# EEZ_DIB_AUX_PS_r1B2.net
KiCad netlist of a schematic drawn in EAGLE
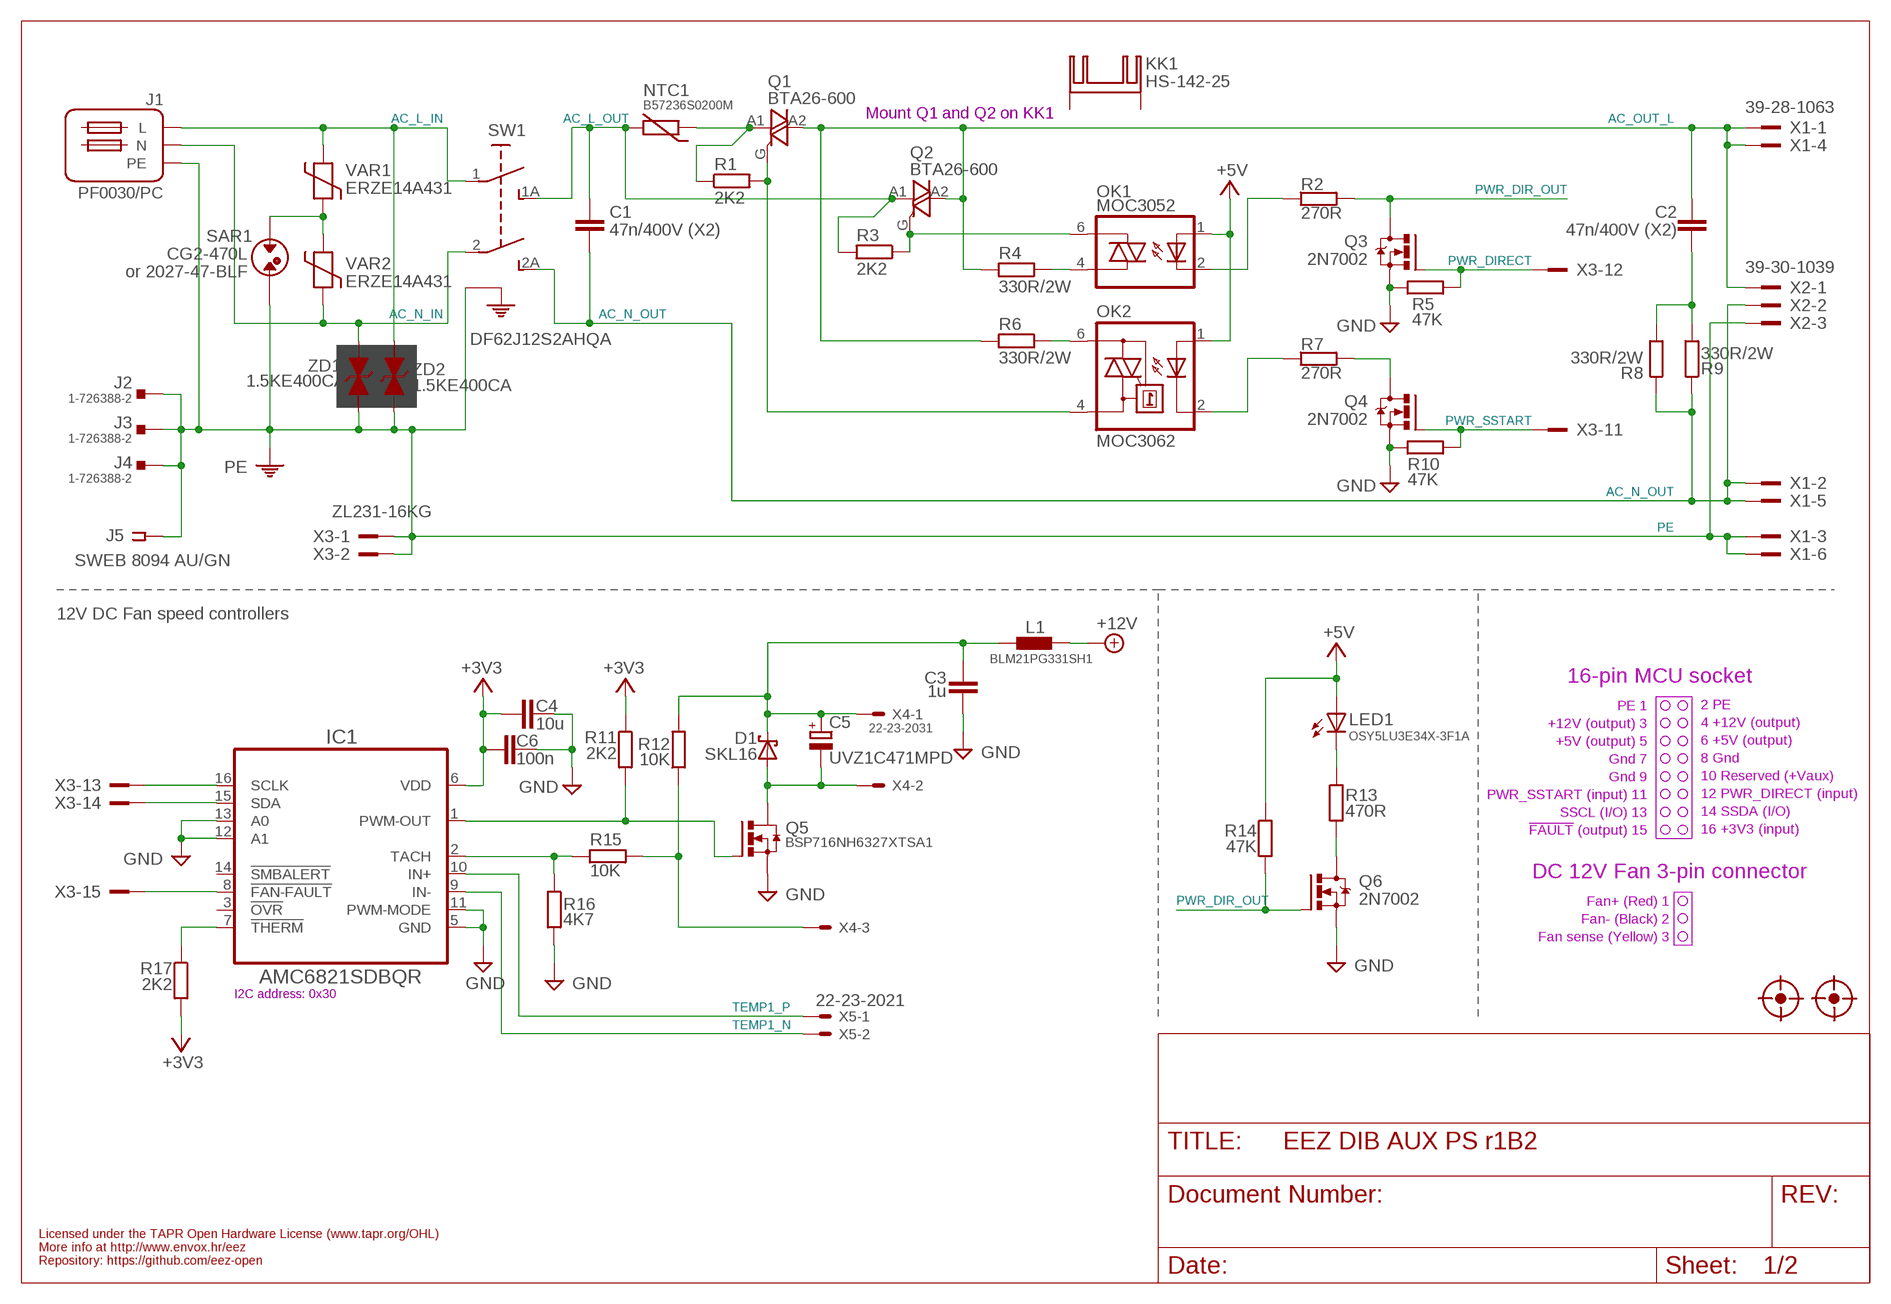
[diagram p0: schematic, sheet 1]
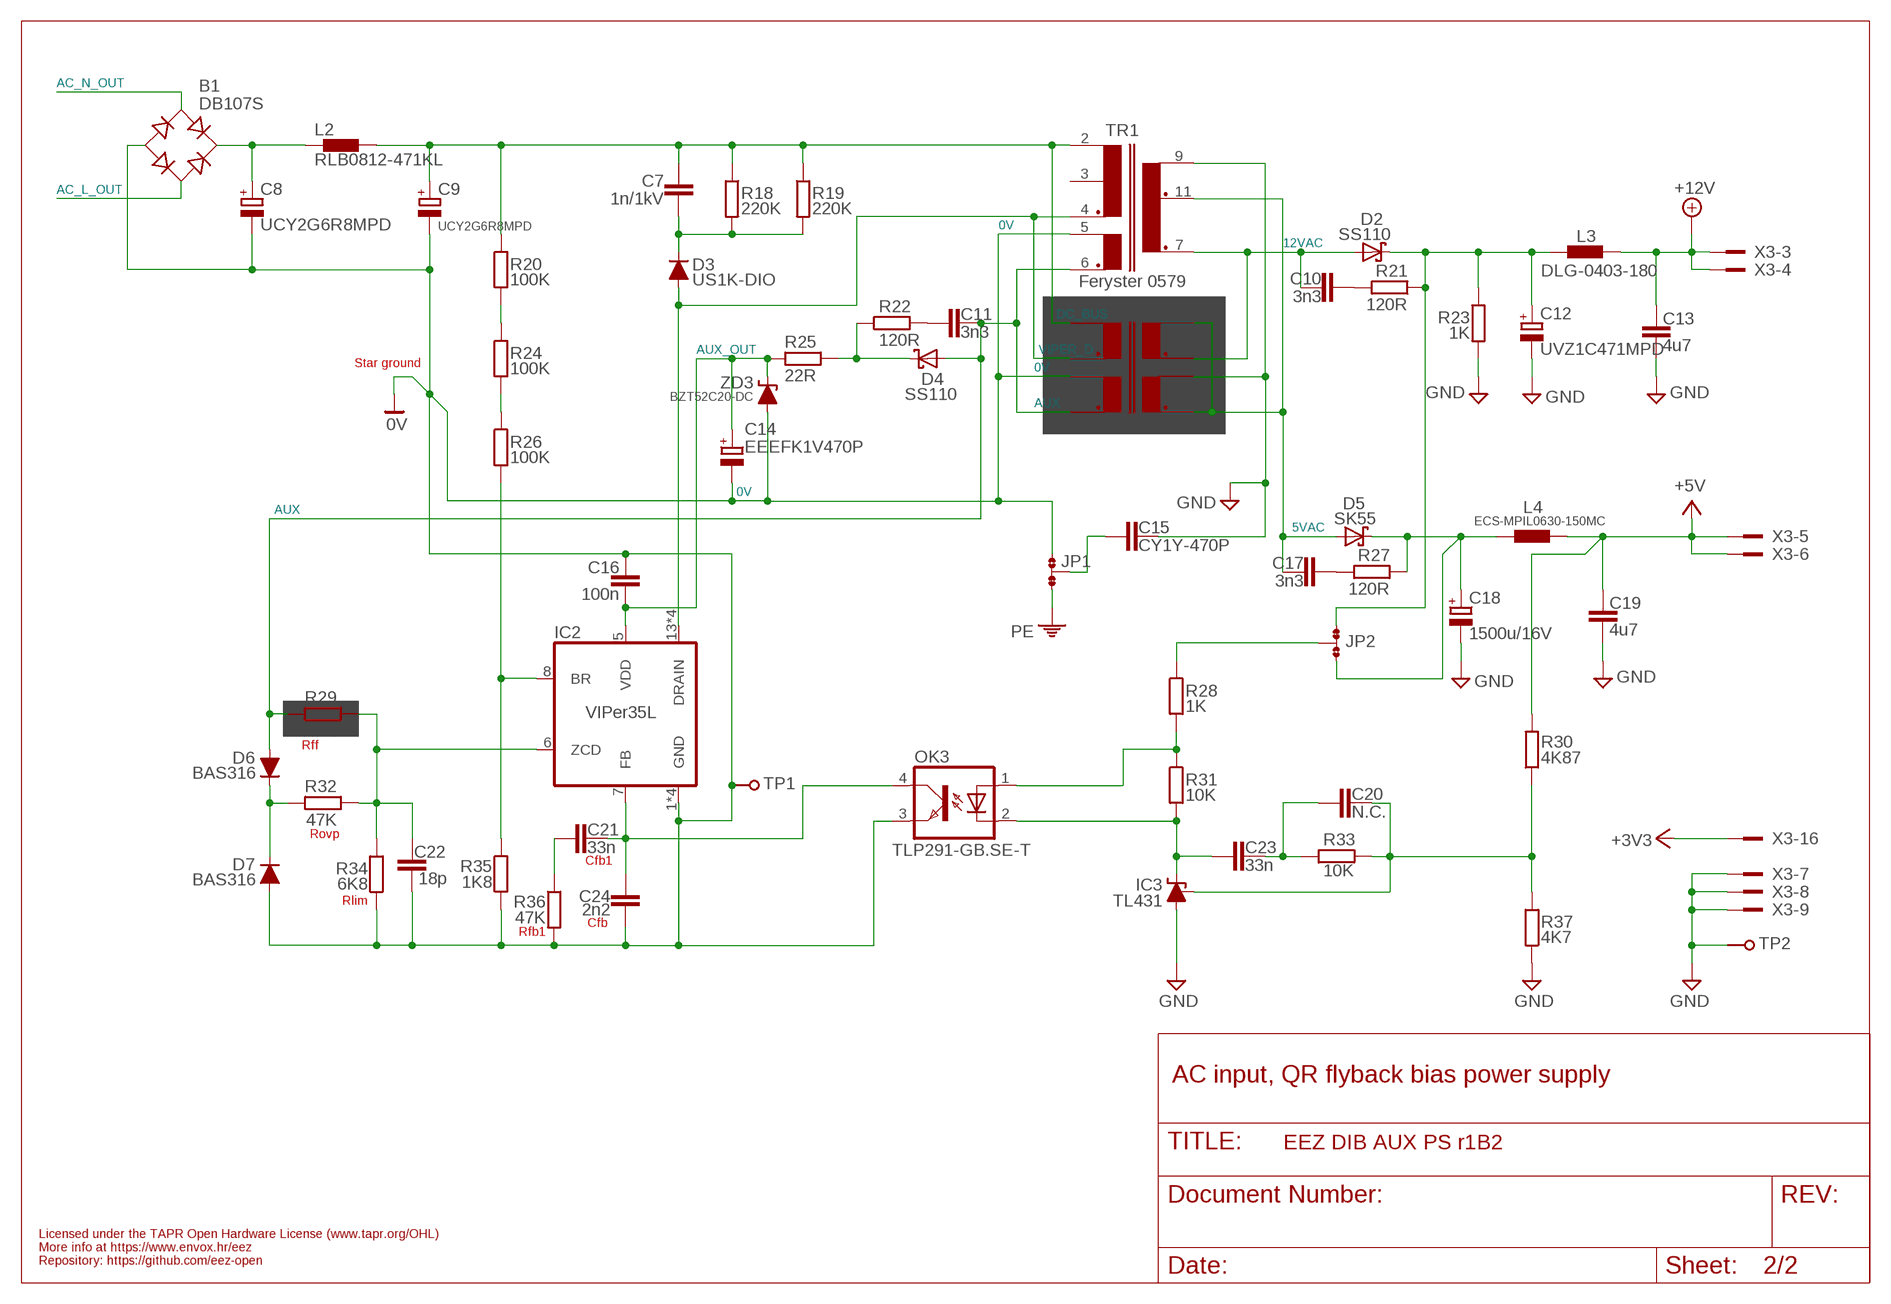
[diagram p1: schematic, sheet 2]

(export (version "E")
  (design (tool "Eeschema 10.0.6"))
  (components
    (comp (ref "C1")
      (value "47n/400V (X2)")
      (footprint "eagle-import:C102-054X133")
      (libsource (lib "eagle-import") (part "C-EU102-054X133"))
    )
    (comp (ref "C2")
      (value "47n/400V (X2)")
      (footprint "eagle-import:C102-054X133")
      (libsource (lib "eagle-import") (part "C-EU102-054X133"))
    )
    (comp (ref "C3")
      (value "1u")
      (footprint "eagle-import:C0805")
      (libsource (lib "eagle-import") (part "C-EUC0805"))
    )
    (comp (ref "C4")
      (value "10u")
      (footprint "eagle-import:C1206")
      (libsource (lib "eagle-import") (part "C-EUC1206"))
    )
    (comp (ref "C5")
      (value "UVZ1C471MPD")
      (footprint "eagle-import:ECAP3.5_8")
      (libsource (lib "eagle-import") (part "ECAP3.5G_8MM"))
    )
    (comp (ref "C6")
      (value "100n")
      (footprint "eagle-import:C0603")
      (libsource (lib "eagle-import") (part "C-EUC0603"))
    )
    (comp (ref "D1")
      (value "SKL16")
      (footprint "eagle-import:SOD123")
      (libsource (lib "eagle-import") (part "SCHOTTKYSOD123"))
    )
    (comp (ref "FM1")
      (value "FIDUCIAL")
      (footprint "eagle-import:FIDUCIAL")
      (libsource (lib "eagle-import") (part "FIDUCIAL"))
    )
    (comp (ref "FM2")
      (value "FIDUCIAL")
      (footprint "eagle-import:FIDUCIAL")
      (libsource (lib "eagle-import") (part "FIDUCIAL"))
    )
    (comp (ref "IC1")
      (value "AMC6821SDBQR")
      (footprint "eagle-import:DBQ16")
      (fields
        (field (name "GENERIC_PART_NUMBER") "AMC6821")
        (field (name "MANUFACTURER") "Texas Instruments")
      )
      (libsource (lib "eagle-import") (part "AMC6821"))
    )
    (comp (ref "J1")
      (value "PF0030/PC")
      (footprint "eagle-import:PF0030_PC")
      (libsource (lib "eagle-import") (part "PF0030/PC"))
    )
    (comp (ref "J2")
      (value "1-726388-2")
      (footprint "eagle-import:PCB_TAB-4.8MM")
      (libsource (lib "eagle-import") (part "PCB_TAB4.8MM"))
    )
    (comp (ref "J3")
      (value "1-726388-2")
      (footprint "eagle-import:PCB_TAB-4.8MM")
      (libsource (lib "eagle-import") (part "PCB_TAB4.8MM"))
    )
    (comp (ref "J4")
      (value "1-726388-2")
      (footprint "eagle-import:PCB_TAB-4.8MM")
      (libsource (lib "eagle-import") (part "PCB_TAB4.8MM"))
    )
    (comp (ref "J5")
      (value "SWEB 8094 AU/GN")
      (footprint "eagle-import:S16N-PC")
      (libsource (lib "eagle-import") (part "BINDING_POSTCLIFF"))
    )
    (comp (ref "KK1")
      (value "HS-142-25")
      (footprint "eagle-import:SK129")
      (libsource (lib "eagle-import") (part "SK129-PAD"))
    )
    (comp (ref "L1")
      (value "BLM21PG331SH1")
      (footprint "eagle-import:0805")
      (libsource (lib "eagle-import") (part "L-EU0805"))
    )
    (comp (ref "LED1")
      (value "OSY5LU3E34X-3F1A")
      (footprint "eagle-import:OSG8")
      (libsource (lib "eagle-import") (part "LEDOSG8"))
    )
    (comp (ref "NTC1")
      (value "B57236S0200M")
      (footprint "eagle-import:NTC_11.5X6_RM5")
      (libsource (lib "eagle-import") (part "NTC11.5X6"))
    )
    (comp (ref "OK1")
      (value "MOC3052")
      (footprint "eagle-import:DIL6-SMD")
      (libsource (lib "eagle-import") (part "MOC305X"))
    )
    (comp (ref "OK2")
      (value "MOC3062")
      (footprint "eagle-import:DIL6-SMD")
      (fields
        (field (name "MF") "FAIRCHILD SEMICONDUCTOR")
        (field (name "MPN") "MOC3033S-M")
        (field (name "MF_1") "FAIRCHILD SEMICONDUCTOR")
        (field (name "MPN_1") "MOC3033S-M")
        (field (name "OC_FARNELL") "unknown")
        (field (name "OC_NEWARK") "05C2878")
      )
      (libsource (lib "eagle-import") (part "MOC30S33"))
    )
    (comp (ref "Q1")
      (value "BTA26-600")
      (footprint "eagle-import:TOP3S-1")
      (libsource (lib "eagle-import") (part "BTA26-V"))
    )
    (comp (ref "Q2")
      (value "BTA26-600")
      (footprint "eagle-import:TOP3S-1")
      (libsource (lib "eagle-import") (part "BTA26-V"))
    )
    (comp (ref "Q3")
      (value "2N7002")
      (footprint "eagle-import:SOT103P240X110-3N")
      (fields (field (name "MPN") "2N7002-7-F"))
      (libsource (lib "eagle-import") (part "2N7002"))
    )
    (comp (ref "Q4")
      (value "2N7002")
      (footprint "eagle-import:SOT103P240X110-3N")
      (fields (field (name "MPN") "2N7002-7-F"))
      (libsource (lib "eagle-import") (part "2N7002"))
    )
    (comp (ref "Q5")
      (value "BSP716NH6327XTSA1")
      (footprint "eagle-import:SOT223")
      (libsource (lib "eagle-import") (part "N-HEXFET-2D_?-SOT232IRLL014N"))
    )
    (comp (ref "Q6")
      (value "2N7002")
      (footprint "eagle-import:SOT103P240X110-3N")
      (fields
        (field (name "MPN") "2N7002-7-F")
        (field (name "MPN_1") "2N7002-7-F")
        (field (name "OC_FARNELL") "1713823")
        (field (name "OC_NEWARK") "25R5679")
        (field (name "PACKAGE") "SOT-23-3")
        (field (name "SUPPLIER") "DIODES INC.")
      )
      (libsource (lib "eagle-import") (part "2N7002"))
    )
    (comp (ref "R1")
      (value "2K2")
      (footprint "eagle-import:R0805")
      (libsource (lib "eagle-import") (part "R-EU_R0805"))
    )
    (comp (ref "R2")
      (value "270R")
      (footprint "eagle-import:R0805")
      (libsource (lib "eagle-import") (part "R-EU_R0805"))
    )
    (comp (ref "R3")
      (value "2K2")
      (footprint "eagle-import:R0805")
      (libsource (lib "eagle-import") (part "R-EU_R0805"))
    )
    (comp (ref "R4")
      (value "330R/2W")
      (footprint "eagle-import:R2512")
      (libsource (lib "eagle-import") (part "R-EU_R2512"))
    )
    (comp (ref "R5")
      (value "47K")
      (footprint "eagle-import:R0805")
      (libsource (lib "eagle-import") (part "R-EU_R0805"))
    )
    (comp (ref "R6")
      (value "330R/2W")
      (footprint "eagle-import:R2512")
      (libsource (lib "eagle-import") (part "R-EU_R2512"))
    )
    (comp (ref "R7")
      (value "270R")
      (footprint "eagle-import:R0805")
      (libsource (lib "eagle-import") (part "R-EU_R0805"))
    )
    (comp (ref "R8")
      (value "330R/2W")
      (footprint "eagle-import:R2512")
      (libsource (lib "eagle-import") (part "R-EU_R2512"))
    )
    (comp (ref "R9")
      (value "330R/2W")
      (footprint "eagle-import:R2512")
      (libsource (lib "eagle-import") (part "R-EU_R2512"))
    )
    (comp (ref "R10")
      (value "47K")
      (footprint "eagle-import:R0805")
      (libsource (lib "eagle-import") (part "R-EU_R0805"))
    )
    (comp (ref "R11")
      (value "2K2")
      (footprint "eagle-import:R0805")
      (libsource (lib "eagle-import") (part "R-EU_R0805"))
    )
    (comp (ref "R12")
      (value "10K")
      (footprint "eagle-import:R0805")
      (libsource (lib "eagle-import") (part "R-EU_R0805"))
    )
    (comp (ref "R13")
      (value "470R")
      (footprint "eagle-import:R0805")
      (libsource (lib "eagle-import") (part "R-EU_R0805"))
    )
    (comp (ref "R14")
      (value "47K")
      (footprint "eagle-import:R0805")
      (libsource (lib "eagle-import") (part "R-EU_R0805"))
    )
    (comp (ref "R15")
      (value "10K")
      (footprint "eagle-import:R0805")
      (libsource (lib "eagle-import") (part "R-EU_R0805"))
    )
    (comp (ref "R16")
      (value "4K7")
      (footprint "eagle-import:R0805")
      (libsource (lib "eagle-import") (part "R-EU_R0805"))
    )
    (comp (ref "R17")
      (value "2K2")
      (footprint "eagle-import:R0805")
      (libsource (lib "eagle-import") (part "R-EU_R0805"))
    )
    (comp (ref "SAR1")
      (value "CG2-470L")
      (footprint "eagle-import:SAR")
      (libsource (lib "eagle-import") (part "SAR"))
    )
    (comp (ref "SW1")
      (value "DF62J12S2AHQA")
      (footprint "eagle-import:DF62J12S2")
      (libsource (lib "eagle-import") (part "DF62J12S2AHQA"))
    )
    (comp (ref "VAR1")
      (value "ERZE14A431")
      (footprint "eagle-import:VARISTOR_13MM")
      (libsource (lib "eagle-import") (part "VARISTOR-13"))
    )
    (comp (ref "VAR2")
      (value "ERZE14A431")
      (footprint "eagle-import:VARISTOR_13MM")
      (libsource (lib "eagle-import") (part "VARISTOR-13"))
    )
    (comp (ref "X1")
      (value "39-28-1063")
      (footprint "eagle-import:MINIFIT_5566-06A_CRE")
      (libsource (lib "eagle-import") (part "MINIFIT_5566-06A-CRE"))
    )
    (comp (ref "X2")
      (value "39-30-1039")
      (footprint "eagle-import:MINIFIT_39301039_CRE")
      (libsource (lib "eagle-import") (part "MINIFIT_39301039-CREEPAGE"))
    )
    (comp (ref "X3")
      (value "ZL231-16KG")
      (footprint "eagle-import:ML16L")
      (libsource (lib "eagle-import") (part "IDC-16PIN-ANGLED"))
    )
    (comp (ref "X4")
      (value "22-23-2031")
      (footprint "eagle-import:22-23-2031")
      (fields (field (name "MF") "MOLEX"))
      (libsource (lib "eagle-import") (part "22-23-2031"))
    )
    (comp (ref "X5")
      (value "22-23-2021")
      (footprint "eagle-import:22-23-2021")
      (fields (field (name "MF") "MOLEX"))
      (libsource (lib "eagle-import") (part "22-23-2021"))
    )
    (comp (ref "ZD1")
      (value "1.5KE400CA")
      (footprint "eagle-import:DO201-BIDIR")
      (libsource (lib "eagle-import") (part "1.5KE-BIDIR"))
    )
    (comp (ref "ZD2")
      (value "1.5KE400CA")
      (footprint "eagle-import:DO201-BIDIR")
      (libsource (lib "eagle-import") (part "1.5KE-BIDIR"))
    )
    (comp (ref "B1")
      (value "DB107S")
      (footprint "eagle-import:DBS")
      (libsource (lib "eagle-import") (part "DB?GS107"))
    )
    (comp (ref "C7")
      (value "1n/1kV")
      (footprint "eagle-import:C1210")
      (libsource (lib "eagle-import") (part "C-EUC1210"))
    )
    (comp (ref "C8")
      (value "UCY2G6R8MPD")
      (footprint "eagle-import:ECAP5_10.5")
      (libsource (lib "eagle-import") (part "ECAP5G_10.5MM"))
    )
    (comp (ref "C9")
      (value "UCY2G6R8MPD")
      (footprint "eagle-import:ECAP5_10.5")
      (libsource (lib "eagle-import") (part "ECAP5G_10.5MM"))
    )
    (comp (ref "C10")
      (value "3n3")
      (footprint "eagle-import:C0805")
      (libsource (lib "eagle-import") (part "C-EUC0805"))
    )
    (comp (ref "C11")
      (value "3n3")
      (footprint "eagle-import:C0805")
      (libsource (lib "eagle-import") (part "C-EUC0805"))
    )
    (comp (ref "C12")
      (value "UVZ1C471MPD")
      (footprint "eagle-import:ECAP3.5_8")
      (libsource (lib "eagle-import") (part "ECAP3.5G_8MM"))
    )
    (comp (ref "C13")
      (value "4u7")
      (footprint "eagle-import:C1210")
      (libsource (lib "eagle-import") (part "C-EUC1210"))
    )
    (comp (ref "C14")
      (value "EEEFK1V470P")
      (footprint "eagle-import:CAPAE660X610N")
      (libsource (lib "eagle-import") (part "ECAPPANASONIC_H"))
    )
    (comp (ref "C15")
      (value "CY1Y-470P")
      (footprint "eagle-import:CY075-032X103")
      (libsource (lib "eagle-import") (part "C-EUCY"))
    )
    (comp (ref "C16")
      (value "100n")
      (footprint "eagle-import:C0603")
      (libsource (lib "eagle-import") (part "C-EUC0603"))
    )
    (comp (ref "C17")
      (value "3n3")
      (footprint "eagle-import:C0805")
      (libsource (lib "eagle-import") (part "C-EUC0805"))
    )
    (comp (ref "C18")
      (value "1500u/16V")
      (footprint "eagle-import:ECAP5_13")
      (libsource (lib "eagle-import") (part "ECAP5G_13MM"))
    )
    (comp (ref "C19")
      (value "4u7")
      (footprint "eagle-import:C1210")
      (libsource (lib "eagle-import") (part "C-EUC1210"))
    )
    (comp (ref "C20")
      (value "N.C.")
      (footprint "eagle-import:C0805")
      (libsource (lib "eagle-import") (part "C-EUC0805"))
    )
    (comp (ref "C21")
      (value "33n")
      (footprint "eagle-import:C0805")
      (libsource (lib "eagle-import") (part "C-EUC0805"))
    )
    (comp (ref "C22")
      (value "18p")
      (footprint "eagle-import:C0603")
      (libsource (lib "eagle-import") (part "C-EUC0603"))
    )
    (comp (ref "C23")
      (value "33n")
      (footprint "eagle-import:C0805")
      (libsource (lib "eagle-import") (part "C-EUC0805"))
    )
    (comp (ref "C24")
      (value "2n2")
      (footprint "eagle-import:C0805")
      (libsource (lib "eagle-import") (part "C-EUC0805"))
    )
    (comp (ref "D2")
      (value "SS110")
      (footprint "eagle-import:SMB")
      (libsource (lib "eagle-import") (part "SCHOTTKYSMB"))
    )
    (comp (ref "D3")
      (value "US1K-DIO")
      (footprint "eagle-import:DO214AA")
      (libsource (lib "eagle-import") (part "DIODEDO214AA"))
    )
    (comp (ref "D4")
      (value "SS110")
      (footprint "eagle-import:SMB")
      (libsource (lib "eagle-import") (part "SCHOTTKYSMB"))
    )
    (comp (ref "D5")
      (value "SK55")
      (footprint "eagle-import:SMB")
      (libsource (lib "eagle-import") (part "SCHOTTKYSMB"))
    )
    (comp (ref "D6")
      (value "BAS316")
      (footprint "eagle-import:SOD323-R")
      (libsource (lib "eagle-import") (part "DIODESOD323R"))
    )
    (comp (ref "D7")
      (value "BAS316")
      (footprint "eagle-import:SOD323-R")
      (libsource (lib "eagle-import") (part "DIODESOD323R"))
    )
    (comp (ref "IC2")
      (value "VIPer35L")
      (footprint "eagle-import:SOIC-16")
      (libsource (lib "eagle-import") (part "VIPER35"))
    )
    (comp (ref "IC3")
      (value "TL431")
      (footprint "eagle-import:SOT103P240X110-3N")
      (libsource (lib "eagle-import") (part "TL431"))
    )
    (comp (ref "JP1")
      (value "JP3-CUT")
      (footprint "eagle-import:JP3-CUT")
      (libsource (lib "eagle-import") (part "JP3-CUT"))
    )
    (comp (ref "JP2")
      (value "JP3-CUT")
      (footprint "eagle-import:JP3-CUT")
      (libsource (lib "eagle-import") (part "JP3-CUT"))
    )
    (comp (ref "L2")
      (value "RLB0812-471KL")
      (footprint "eagle-import:FERSYTER_DSZ6")
      (libsource (lib "eagle-import") (part "FERYSTER_DSZ6"))
    )
    (comp (ref "L3")
      (value "DLG-0403-180")
      (footprint "eagle-import:DE0403")
      (libsource (lib "eagle-import") (part "EEZ_inductors_and_transformers_DE0403"))
    )
    (comp (ref "L4")
      (value "ECS-MPIL0630-150MC")
      (footprint "eagle-import:DE0704")
      (libsource (lib "eagle-import") (part "DE0704"))
    )
    (comp (ref "OK3")
      (value "TLP291-GB.SE-T")
      (footprint "eagle-import:SO4")
      (libsource (lib "eagle-import") (part "TLP291"))
    )
    (comp (ref "R18")
      (value "220K")
      (footprint "eagle-import:R1206")
      (libsource (lib "eagle-import") (part "R-EU_R1206"))
    )
    (comp (ref "R19")
      (value "220K")
      (footprint "eagle-import:R1206")
      (libsource (lib "eagle-import") (part "R-EU_R1206"))
    )
    (comp (ref "R20")
      (value "100K")
      (footprint "eagle-import:R1206")
      (libsource (lib "eagle-import") (part "R-EU_R1206"))
    )
    (comp (ref "R21")
      (value "120R")
      (footprint "eagle-import:R0805")
      (libsource (lib "eagle-import") (part "R-EU_R0805"))
    )
    (comp (ref "R22")
      (value "120R")
      (footprint "eagle-import:R0805")
      (libsource (lib "eagle-import") (part "R-EU_R0805"))
    )
    (comp (ref "R23")
      (value "1K")
      (footprint "eagle-import:R0805")
      (libsource (lib "eagle-import") (part "R-EU_R0805"))
    )
    (comp (ref "R24")
      (value "100K")
      (footprint "eagle-import:R1206")
      (libsource (lib "eagle-import") (part "R-EU_R1206"))
    )
    (comp (ref "R25")
      (value "22R")
      (footprint "eagle-import:R0805")
      (libsource (lib "eagle-import") (part "R-EU_R0805"))
    )
    (comp (ref "R26")
      (value "100K")
      (footprint "eagle-import:R1206")
      (libsource (lib "eagle-import") (part "R-EU_R1206"))
    )
    (comp (ref "R27")
      (value "120R")
      (footprint "eagle-import:R0805")
      (libsource (lib "eagle-import") (part "R-EU_R0805"))
    )
    (comp (ref "R28")
      (value "1K")
      (footprint "eagle-import:R0805")
      (libsource (lib "eagle-import") (part "R-EU_R0805"))
    )
    (comp (ref "R29")
      (value "N.C.")
      (footprint "eagle-import:R0805")
      (libsource (lib "eagle-import") (part "R-EU_R0805"))
    )
    (comp (ref "R30")
      (value "4K87")
      (footprint "eagle-import:R0805")
      (libsource (lib "eagle-import") (part "R-EU_R0805"))
    )
    (comp (ref "R31")
      (value "10K")
      (footprint "eagle-import:R0805")
      (libsource (lib "eagle-import") (part "R-EU_R0805"))
    )
    (comp (ref "R32")
      (value "47K")
      (footprint "eagle-import:R0805")
      (libsource (lib "eagle-import") (part "R-EU_R0805"))
    )
    (comp (ref "R33")
      (value "10K")
      (footprint "eagle-import:R0805")
      (libsource (lib "eagle-import") (part "R-EU_R0805"))
    )
    (comp (ref "R34")
      (value "6K8")
      (footprint "eagle-import:R0805")
      (libsource (lib "eagle-import") (part "R-EU_R0805"))
    )
    (comp (ref "R35")
      (value "1K8")
      (footprint "eagle-import:R0805")
      (libsource (lib "eagle-import") (part "R-EU_R0805"))
    )
    (comp (ref "R36")
      (value "47K")
      (footprint "eagle-import:R0805")
      (libsource (lib "eagle-import") (part "R-EU_R0805"))
    )
    (comp (ref "R37")
      (value "4K7")
      (footprint "eagle-import:R0805")
      (libsource (lib "eagle-import") (part "R-EU_R0805"))
    )
    (comp (ref "TP1")
      (value "PCB_TEST_TABSHIELD")
      (footprint "eagle-import:PCB_SHIELD_TAB")
      (libsource (lib "eagle-import") (part "PCB_TEST_TABSHIELD"))
    )
    (comp (ref "TP2")
      (value "PCB_TEST_TABSHIELD")
      (footprint "eagle-import:PCB_SHIELD_TAB")
      (libsource (lib "eagle-import") (part "PCB_TEST_TABSHIELD"))
    )
    (comp (ref "TR1")
      (value "Feryster 0579")
      (footprint "eagle-import:FERYSTER_0579")
      (libsource (lib "eagle-import") (part "FERYSTER_0579"))
    )
    (comp (ref "TR1B")
      (value "(WE 760875532)")
      (footprint "eagle-import:WE-UOST")
      (libsource (lib "eagle-import") (part "WE-UOST"))
    )
    (comp (ref "ZD3")
      (value "BZT52C20-DC")
      (footprint "eagle-import:SOD123")
      (libsource (lib "eagle-import") (part "ZENER-DIODESOD123"))
    )
  )
  (nets
    (net (code "1") (name "+3V3") (class "Default")
      (node (ref "C4") (pin "2") (pinfunction "2_2") (pintype "passive"))
      (node (ref "C6") (pin "2") (pinfunction "2_2") (pintype "passive"))
      (node (ref "IC1") (pin "6") (pinfunction "VDD_6") (pintype "power_in"))
      (node (ref "R11") (pin "1") (pinfunction "1_1") (pintype "passive"))
      (node (ref "R17") (pin "2") (pinfunction "2_2") (pintype "passive"))
      (node (ref "X3") (pin "16") (pinfunction "1_16") (pintype "passive"))
    )
    (net (code "2") (name "+5V") (class "Default")
      (node (ref "C19") (pin "1") (pinfunction "1_1") (pintype "passive"))
      (node (ref "L4") (pin "2") (pinfunction "2_2") (pintype "passive"))
      (node (ref "LED1") (pin "A") (pinfunction "A_A") (pintype "passive"))
      (node (ref "OK1") (pin "1") (pinfunction "A_1") (pintype "passive"))
      (node (ref "OK2") (pin "1") (pinfunction "A_1") (pintype "passive"))
      (node (ref "R14") (pin "1") (pinfunction "1_1") (pintype "passive"))
      (node (ref "R30") (pin "2") (pinfunction "2_2") (pintype "passive"))
      (node (ref "X3") (pin "5") (pinfunction "1_5") (pintype "passive"))
      (node (ref "X3") (pin "6") (pinfunction "1_6") (pintype "passive"))
    )
    (net (code "3") (name "+12V") (class "Default")
      (node (ref "C13") (pin "1") (pinfunction "1_1") (pintype "passive"))
      (node (ref "L1") (pin "2") (pinfunction "2_2") (pintype "passive"))
      (node (ref "L3") (pin "2") (pinfunction "2_2") (pintype "passive"))
      (node (ref "X3") (pin "3") (pinfunction "1_3") (pintype "passive"))
      (node (ref "X3") (pin "4") (pinfunction "1_4") (pintype "passive"))
    )
    (net (code "4") (name "0V") (class "Default")
      (node (ref "B1") (pin "-") (pinfunction "-_-") (pintype "passive"))
      (node (ref "C14") (pin "2") (pinfunction "-_2") (pintype "passive"))
      (node (ref "C16") (pin "1") (pinfunction "1_1") (pintype "passive"))
      (node (ref "C22") (pin "2") (pinfunction "2_2") (pintype "passive"))
      (node (ref "C24") (pin "2") (pinfunction "2_2") (pintype "passive"))
      (node (ref "C8") (pin "-") (pinfunction "-_-") (pintype "passive"))
      (node (ref "C9") (pin "-") (pinfunction "-_-") (pintype "passive"))
      (node (ref "D7") (pin "A") (pinfunction "A_A") (pintype "passive"))
      (node (ref "IC2") (pin "1") (pinfunction "GND_1") (pintype "passive"))
      (node (ref "IC2") (pin "2") (pinfunction "GND_2") (pintype "passive"))
      (node (ref "IC2") (pin "3") (pinfunction "GND_3") (pintype "passive"))
      (node (ref "IC2") (pin "4") (pinfunction "GND_4") (pintype "passive"))
      (node (ref "JP1") (pin "NO") (pinfunction "NO_NO") (pintype "passive"))
      (node (ref "OK3") (pin "3") (pinfunction "EMIT_3") (pintype "passive"))
      (node (ref "R34") (pin "1") (pinfunction "1_1") (pintype "passive"))
      (node (ref "R35") (pin "2") (pinfunction "2_2") (pintype "passive"))
      (node (ref "R36") (pin "2") (pinfunction "2_2") (pintype "passive"))
      (node (ref "TP1") (pin "1") (pinfunction "P$1_1") (pintype "bidirectional"))
      (node (ref "TR1") (pin "5") (pinfunction "AUX_5") (pintype "passive"))
      (node (ref "TR1B") (pin "11") (pinfunction "AUX_11") (pintype "passive"))
      (node (ref "ZD3") (pin "A") (pinfunction "A_A") (pintype "passive"))
    )
    (net (code "5") (name "5VAC") (class "Default")
      (node (ref "C17") (pin "2") (pinfunction "2_2") (pintype "passive"))
      (node (ref "D5") (pin "A") (pinfunction "A_A") (pintype "passive"))
      (node (ref "TR1") (pin "11") (pinfunction "S1_DOT_11") (pintype "passive"))
      (node (ref "TR1B") (pin "2") (pinfunction "S1_2") (pintype "passive"))
      (node (ref "TR1B") (pin "3") (pinfunction "S2_DOT_3") (pintype "passive"))
      (node (ref "TR1B") (pin "4") (pinfunction "S2_DOT_4") (pintype "passive"))
    )
    (net (code "6") (name "12VAC") (class "Default")
      (node (ref "C10") (pin "2") (pinfunction "2_2") (pintype "passive"))
      (node (ref "D2") (pin "A") (pinfunction "A_A") (pintype "passive"))
      (node (ref "TR1") (pin "7") (pinfunction "S2_DOT_7") (pintype "passive"))
      (node (ref "TR1B") (pin "1") (pinfunction "S1_DOT_1") (pintype "passive"))
    )
    (net (code "7") (name "AC_L_IN") (class "Default")
      (node (ref "J1") (pin "L") (pinfunction "L_L") (pintype "bidirectional"))
      (node (ref "SW1") (pin "1") (pinfunction "P_1") (pintype "passive"))
      (node (ref "VAR1") (pin "2") (pinfunction "P$2_2") (pintype "bidirectional"))
      (node (ref "ZD2") (pin "A") (pinfunction "2_A") (pintype "passive"))
    )
    (net (code "8") (name "AC_L_OUT") (class "Default")
      (node (ref "B1") (pin "AC2") (pinfunction "AC2_AC2") (pintype "passive"))
      (node (ref "C1") (pin "1") (pinfunction "1_1") (pintype "passive"))
      (node (ref "NTC1") (pin "1") (pinfunction "P$1_1") (pintype "bidirectional"))
      (node (ref "Q2") (pin "A1") (pinfunction "A1_A1") (pintype "passive"))
      (node (ref "R3") (pin "2") (pinfunction "2_2") (pintype "passive"))
      (node (ref "SW1") (pin "1A") (pinfunction "S_1A") (pintype "passive"))
    )
    (net (code "9") (name "AC_N_IN") (class "Default")
      (node (ref "J1") (pin "N") (pinfunction "N_N") (pintype "bidirectional"))
      (node (ref "SW1") (pin "2") (pinfunction "P1_2") (pintype "passive"))
      (node (ref "VAR2") (pin "1") (pinfunction "P$1_1") (pintype "bidirectional"))
      (node (ref "ZD1") (pin "A") (pinfunction "2_A") (pintype "passive"))
    )
    (net (code "10") (name "AC_N_OUT") (class "Default")
      (node (ref "B1") (pin "AC1") (pinfunction "AC1_AC1") (pintype "passive"))
      (node (ref "C1") (pin "2") (pinfunction "2_2") (pintype "passive"))
      (node (ref "R8") (pin "1") (pinfunction "1_1") (pintype "passive"))
      (node (ref "R9") (pin "1") (pinfunction "1_1") (pintype "passive"))
      (node (ref "SW1") (pin "2A") (pinfunction "S1_2A") (pintype "passive"))
      (node (ref "X1") (pin "2") (pinfunction "1_2") (pintype "passive"))
      (node (ref "X1") (pin "5") (pinfunction "1_5") (pintype "passive"))
      (node (ref "X2") (pin "2") (pinfunction "1_2") (pintype "passive"))
    )
    (net (code "11") (name "AC_OUT_L") (class "Default")
      (node (ref "C2") (pin "1") (pinfunction "1_1") (pintype "passive"))
      (node (ref "Q1") (pin "A2") (pinfunction "A2_A2") (pintype "passive"))
      (node (ref "Q2") (pin "A2") (pinfunction "A2_A2") (pintype "passive"))
      (node (ref "R4") (pin "2") (pinfunction "2_2") (pintype "passive"))
      (node (ref "R6") (pin "2") (pinfunction "2_2") (pintype "passive"))
      (node (ref "X1") (pin "1") (pinfunction "1_1") (pintype "passive"))
      (node (ref "X1") (pin "4") (pinfunction "1_4") (pintype "passive"))
      (node (ref "X2") (pin "1") (pinfunction "1_1") (pintype "passive"))
    )
    (net (code "12") (name "AUX") (class "Default")
      (node (ref "C11") (pin "2") (pinfunction "2_2") (pintype "passive"))
      (node (ref "D4") (pin "A") (pinfunction "A_A") (pintype "passive"))
      (node (ref "D6") (pin "A") (pinfunction "A_A") (pintype "passive"))
      (node (ref "R29") (pin "2") (pinfunction "2_2") (pintype "passive"))
      (node (ref "TR1") (pin "6") (pinfunction "AUX_DOT_6") (pintype "passive"))
      (node (ref "TR1B") (pin "12") (pinfunction "AUX_DOT_12") (pintype "passive"))
    )
    (net (code "13") (name "AUX_OUT") (class "Default")
      (node (ref "C14") (pin "1") (pinfunction "+_1") (pintype "passive"))
      (node (ref "C16") (pin "2") (pinfunction "2_2") (pintype "passive"))
      (node (ref "IC2") (pin "5") (pinfunction "VDD_5") (pintype "power_in"))
      (node (ref "R25") (pin "2") (pinfunction "2_2") (pintype "passive"))
      (node (ref "ZD3") (pin "C") (pinfunction "C_C") (pintype "passive"))
    )
    (net (code "14") (name "DC_BUS") (class "Default")
      (node (ref "C7") (pin "1") (pinfunction "1_1") (pintype "passive"))
      (node (ref "C9") (pin "+") (pinfunction "+_+") (pintype "passive"))
      (node (ref "L2") (pin "P$2") (pinfunction "2_P$2") (pintype "passive"))
      (node (ref "R18") (pin "1") (pinfunction "1_1") (pintype "passive"))
      (node (ref "R19") (pin "1") (pinfunction "1_1") (pintype "passive"))
      (node (ref "R20") (pin "1") (pinfunction "1_1") (pintype "passive"))
      (node (ref "TR1") (pin "2") (pinfunction "P1_2") (pintype "passive"))
      (node (ref "TR1B") (pin "7") (pinfunction "P1_7") (pintype "passive"))
    )
    (net (code "15") (name "GND") (class "Default")
      (node (ref "C12") (pin "-") (pinfunction "-_-") (pintype "passive"))
      (node (ref "C13") (pin "2") (pinfunction "2_2") (pintype "passive"))
      (node (ref "C15") (pin "2") (pinfunction "2_2") (pintype "passive"))
      (node (ref "C18") (pin "-") (pinfunction "-_-") (pintype "passive"))
      (node (ref "C19") (pin "2") (pinfunction "2_2") (pintype "passive"))
      (node (ref "C3") (pin "2") (pinfunction "2_2") (pintype "passive"))
      (node (ref "C4") (pin "1") (pinfunction "1_1") (pintype "passive"))
      (node (ref "C6") (pin "1") (pinfunction "1_1") (pintype "passive"))
      (node (ref "IC1") (pin "11") (pinfunction "PWM-MODE_11") (pintype "input"))
      (node (ref "IC1") (pin "12") (pinfunction "A1_12") (pintype "passive"))
      (node (ref "IC1") (pin "13") (pinfunction "A0_13") (pintype "passive"))
      (node (ref "IC1") (pin "5") (pinfunction "GND_5") (pintype "power_in"))
      (node (ref "IC3") (pin "3") (pinfunction "A_3") (pintype "passive"))
      (node (ref "Q3") (pin "2") (pinfunction "S_2") (pintype "passive"))
      (node (ref "Q4") (pin "2") (pinfunction "S_2") (pintype "passive"))
      (node (ref "Q5") (pin "3") (pinfunction "S_3") (pintype "passive"))
      (node (ref "Q6") (pin "2") (pinfunction "S_2") (pintype "passive"))
      (node (ref "R10") (pin "1") (pinfunction "1_1") (pintype "passive"))
      (node (ref "R16") (pin "2") (pinfunction "2_2") (pintype "passive"))
      (node (ref "R23") (pin "2") (pinfunction "2_2") (pintype "passive"))
      (node (ref "R37") (pin "1") (pinfunction "1_1") (pintype "passive"))
      (node (ref "R5") (pin "1") (pinfunction "1_1") (pintype "passive"))
      (node (ref "TP2") (pin "1") (pinfunction "P$1_1") (pintype "bidirectional"))
      (node (ref "TR1") (pin "9") (pinfunction "S_COMM_9") (pintype "passive"))
      (node (ref "TR1B") (pin "5") (pinfunction "S2_5") (pintype "passive"))
      (node (ref "TR1B") (pin "6") (pinfunction "S2_6") (pintype "passive"))
      (node (ref "X3") (pin "7") (pinfunction "1_7") (pintype "passive"))
      (node (ref "X3") (pin "8") (pinfunction "1_8") (pintype "passive"))
      (node (ref "X3") (pin "9") (pinfunction "1_9") (pintype "passive"))
    )
    (net (code "16") (name "Net-(C2-Pad2)") (class "Default")
      (node (ref "C2") (pin "2") (pinfunction "2_2") (pintype "passive"))
      (node (ref "R8") (pin "2") (pinfunction "2_2") (pintype "passive"))
      (node (ref "R9") (pin "2") (pinfunction "2_2") (pintype "passive"))
    )
    (net (code "17") (name "Net-(C7-Pad2)") (class "Default")
      (node (ref "C7") (pin "2") (pinfunction "2_2") (pintype "passive"))
      (node (ref "D3") (pin "C") (pinfunction "C_C") (pintype "passive"))
      (node (ref "R18") (pin "2") (pinfunction "2_2") (pintype "passive"))
      (node (ref "R19") (pin "2") (pinfunction "2_2") (pintype "passive"))
    )
    (net (code "18") (name "Net-(C10-Pad1)") (class "Default")
      (node (ref "C10") (pin "1") (pinfunction "1_1") (pintype "passive"))
      (node (ref "R21") (pin "2") (pinfunction "2_2") (pintype "passive"))
    )
    (net (code "19") (name "Net-(C11-Pad1)") (class "Default")
      (node (ref "C11") (pin "1") (pinfunction "1_1") (pintype "passive"))
      (node (ref "R22") (pin "2") (pinfunction "2_2") (pintype "passive"))
    )
    (net (code "20") (name "Net-(C12-Pad+)") (class "Default")
      (node (ref "C12") (pin "+") (pinfunction "+_+") (pintype "passive"))
      (node (ref "D2") (pin "C") (pinfunction "C_C") (pintype "passive"))
      (node (ref "JP2") (pin "NC") (pinfunction "NC_NC") (pintype "passive"))
      (node (ref "L3") (pin "1") (pinfunction "1_1") (pintype "passive"))
      (node (ref "R21") (pin "1") (pinfunction "1_1") (pintype "passive"))
      (node (ref "R23") (pin "1") (pinfunction "1_1") (pintype "passive"))
    )
    (net (code "21") (name "Net-(C15-Pad1)") (class "Default")
      (node (ref "C15") (pin "1") (pinfunction "1_1") (pintype "passive"))
      (node (ref "JP1") (pin "COM") (pinfunction "COM_COM") (pintype "passive"))
    )
    (net (code "22") (name "Net-(C17-Pad1)") (class "Default")
      (node (ref "C17") (pin "1") (pinfunction "1_1") (pintype "passive"))
      (node (ref "R27") (pin "2") (pinfunction "2_2") (pintype "passive"))
    )
    (net (code "23") (name "Net-(C18-Pad+)") (class "Default")
      (node (ref "C18") (pin "+") (pinfunction "+_+") (pintype "passive"))
      (node (ref "D5") (pin "C") (pinfunction "C_C") (pintype "passive"))
      (node (ref "JP2") (pin "NO") (pinfunction "NO_NO") (pintype "passive"))
      (node (ref "L4") (pin "1") (pinfunction "1_1") (pintype "passive"))
      (node (ref "R27") (pin "1") (pinfunction "1_1") (pintype "passive"))
    )
    (net (code "24") (name "Net-(C20-Pad1)") (class "Default")
      (node (ref "C20") (pin "1") (pinfunction "1_1") (pintype "passive"))
      (node (ref "C23") (pin "2") (pinfunction "2_2") (pintype "passive"))
      (node (ref "R33") (pin "1") (pinfunction "1_1") (pintype "passive"))
    )
    (net (code "25") (name "Net-(C21-Pad1)") (class "Default")
      (node (ref "C21") (pin "1") (pinfunction "1_1") (pintype "passive"))
      (node (ref "R36") (pin "1") (pinfunction "1_1") (pintype "passive"))
    )
    (net (code "26") (name "Net-(D4-PadC)") (class "Default")
      (node (ref "D4") (pin "C") (pinfunction "C_C") (pintype "passive"))
      (node (ref "R22") (pin "1") (pinfunction "1_1") (pintype "passive"))
      (node (ref "R25") (pin "1") (pinfunction "1_1") (pintype "passive"))
    )
    (net (code "27") (name "Net-(D6-PadC)") (class "Default")
      (node (ref "D6") (pin "C") (pinfunction "C_C") (pintype "passive"))
      (node (ref "D7") (pin "C") (pinfunction "C_C") (pintype "passive"))
      (node (ref "R32") (pin "2") (pinfunction "2_2") (pintype "passive"))
    )
    (net (code "28") (name "Net-(IC1-PWM-OUT)") (class "Default")
      (node (ref "IC1") (pin "1") (pinfunction "PWM-OUT_1") (pintype "output"))
      (node (ref "Q5") (pin "1") (pinfunction "G_1") (pintype "passive"))
      (node (ref "R11") (pin "2") (pinfunction "2_2") (pintype "passive"))
    )
    (net (code "29") (name "Net-(IC1-SCLK)") (class "Default")
      (node (ref "IC1") (pin "16") (pinfunction "SCLK_16") (pintype "input"))
      (node (ref "X3") (pin "13") (pinfunction "1_13") (pintype "passive"))
    )
    (net (code "30") (name "Net-(IC1-SDA)") (class "Default")
      (node (ref "IC1") (pin "15") (pinfunction "SDA_15") (pintype "bidirectional"))
      (node (ref "X3") (pin "14") (pinfunction "1_14") (pintype "passive"))
    )
    (net (code "31") (name "Net-(IC1-TACH)") (class "Default")
      (node (ref "IC1") (pin "2") (pinfunction "TACH_2") (pintype "input"))
      (node (ref "R15") (pin "1") (pinfunction "1_1") (pintype "passive"))
      (node (ref "R16") (pin "1") (pinfunction "1_1") (pintype "passive"))
    )
    (net (code "32") (name "Net-(IC1-~{FAN-FAULT})") (class "Default")
      (node (ref "IC1") (pin "8") (pinfunction "~{FAN-FAULT}_8") (pintype "output"))
      (node (ref "X3") (pin "15") (pinfunction "1_15") (pintype "passive"))
    )
    (net (code "33") (name "Net-(IC1-~{THERM})") (class "Default")
      (node (ref "IC1") (pin "7") (pinfunction "~{THERM}_7") (pintype "bidirectional"))
      (node (ref "R17") (pin "1") (pinfunction "1_1") (pintype "passive"))
    )
    (net (code "34") (name "Net-(IC2-BR)") (class "Default")
      (node (ref "IC2") (pin "8") (pinfunction "BR_8") (pintype "input"))
      (node (ref "R26") (pin "2") (pinfunction "2_2") (pintype "passive"))
      (node (ref "R35") (pin "1") (pinfunction "1_1") (pintype "passive"))
    )
    (net (code "35") (name "Net-(IC2-FB)") (class "Default")
      (node (ref "C21") (pin "2") (pinfunction "2_2") (pintype "passive"))
      (node (ref "C24") (pin "1") (pinfunction "1_1") (pintype "passive"))
      (node (ref "IC2") (pin "7") (pinfunction "FB_7") (pintype "input"))
      (node (ref "OK3") (pin "4") (pinfunction "COL_4") (pintype "passive"))
    )
    (net (code "36") (name "Net-(IC2-ZCD)") (class "Default")
      (node (ref "C22") (pin "1") (pinfunction "1_1") (pintype "passive"))
      (node (ref "IC2") (pin "6") (pinfunction "ZCD_6") (pintype "input"))
      (node (ref "R29") (pin "1") (pinfunction "1_1") (pintype "passive"))
      (node (ref "R32") (pin "1") (pinfunction "1_1") (pintype "passive"))
      (node (ref "R34") (pin "2") (pinfunction "2_2") (pintype "passive"))
    )
    (net (code "37") (name "Net-(IC3-C)") (class "Default")
      (node (ref "C23") (pin "1") (pinfunction "1_1") (pintype "passive"))
      (node (ref "IC3") (pin "1") (pinfunction "C_1") (pintype "passive"))
      (node (ref "OK3") (pin "2") (pinfunction "C_2") (pintype "passive"))
      (node (ref "R31") (pin "2") (pinfunction "2_2") (pintype "passive"))
    )
    (net (code "38") (name "Net-(IC3-REF)") (class "Default")
      (node (ref "C20") (pin "2") (pinfunction "2_2") (pintype "passive"))
      (node (ref "IC3") (pin "2") (pinfunction "REF_2") (pintype "passive"))
      (node (ref "R30") (pin "1") (pinfunction "1_1") (pintype "passive"))
      (node (ref "R33") (pin "2") (pinfunction "2_2") (pintype "passive"))
      (node (ref "R37") (pin "2") (pinfunction "2_2") (pintype "passive"))
    )
    (net (code "39") (name "Net-(JP2-PadCOM)") (class "Default")
      (node (ref "JP2") (pin "COM") (pinfunction "COM_COM") (pintype "passive"))
      (node (ref "R28") (pin "1") (pinfunction "1_1") (pintype "passive"))
    )
    (net (code "40") (name "Net-(L2-1)") (class "Default")
      (node (ref "B1") (pin "+") (pinfunction "+_+") (pintype "passive"))
      (node (ref "C8") (pin "+") (pinfunction "+_+") (pintype "passive"))
      (node (ref "L2") (pin "P$1") (pinfunction "1_P$1") (pintype "passive"))
    )
    (net (code "41") (name "Net-(LED1-PadC)") (class "Default")
      (node (ref "LED1") (pin "C") (pinfunction "C_C") (pintype "passive"))
      (node (ref "R13") (pin "1") (pinfunction "1_1") (pintype "passive"))
    )
    (net (code "42") (name "Net-(NTC1-P$2)") (class "Default")
      (node (ref "NTC1") (pin "2") (pinfunction "P$2_2") (pintype "bidirectional"))
      (node (ref "Q1") (pin "A1") (pinfunction "A1_A1") (pintype "passive"))
      (node (ref "R1") (pin "1") (pinfunction "1_1") (pintype "passive"))
    )
    (net (code "43") (name "Net-(OK1-A1)") (class "Default")
      (node (ref "OK1") (pin "4") (pinfunction "A1_4") (pintype "passive"))
      (node (ref "R4") (pin "1") (pinfunction "1_1") (pintype "passive"))
    )
    (net (code "44") (name "Net-(OK1-A2)") (class "Default")
      (node (ref "OK1") (pin "6") (pinfunction "A2_6") (pintype "passive"))
      (node (ref "Q2") (pin "G") (pinfunction "G_G") (pintype "passive"))
      (node (ref "R3") (pin "1") (pinfunction "1_1") (pintype "passive"))
    )
    (net (code "45") (name "Net-(OK1-C)") (class "Default")
      (node (ref "OK1") (pin "2") (pinfunction "C_2") (pintype "passive"))
      (node (ref "R2") (pin "1") (pinfunction "1_1") (pintype "passive"))
    )
    (net (code "46") (name "Net-(OK2-A1)") (class "Default")
      (node (ref "OK2") (pin "4") (pinfunction "A1_4") (pintype "passive"))
      (node (ref "Q1") (pin "G") (pinfunction "G_G") (pintype "passive"))
      (node (ref "R1") (pin "2") (pinfunction "2_2") (pintype "passive"))
    )
    (net (code "47") (name "Net-(OK2-A2)") (class "Default")
      (node (ref "OK2") (pin "6") (pinfunction "A2_6") (pintype "passive"))
      (node (ref "R6") (pin "1") (pinfunction "1_1") (pintype "passive"))
    )
    (net (code "48") (name "Net-(OK2-C)") (class "Default")
      (node (ref "OK2") (pin "2") (pinfunction "C_2") (pintype "passive"))
      (node (ref "R7") (pin "1") (pinfunction "1_1") (pintype "passive"))
    )
    (net (code "49") (name "Net-(OK3-A)") (class "Default")
      (node (ref "OK3") (pin "1") (pinfunction "A_1") (pintype "passive"))
      (node (ref "R28") (pin "2") (pinfunction "2_2") (pintype "passive"))
      (node (ref "R31") (pin "1") (pinfunction "1_1") (pintype "passive"))
    )
    (net (code "50") (name "Net-(Q4-D)") (class "Default")
      (node (ref "Q4") (pin "3") (pinfunction "D_3") (pintype "passive"))
      (node (ref "R7") (pin "2") (pinfunction "2_2") (pintype "passive"))
    )
    (net (code "51") (name "Net-(Q6-D)") (class "Default")
      (node (ref "Q6") (pin "3") (pinfunction "D_3") (pintype "passive"))
      (node (ref "R13") (pin "2") (pinfunction "2_2") (pintype "passive"))
    )
    (net (code "52") (name "Net-(R20-Pad2)") (class "Default")
      (node (ref "R20") (pin "2") (pinfunction "2_2") (pintype "passive"))
      (node (ref "R24") (pin "1") (pinfunction "1_1") (pintype "passive"))
    )
    (net (code "53") (name "Net-(R24-Pad2)") (class "Default")
      (node (ref "R24") (pin "2") (pinfunction "2_2") (pintype "passive"))
      (node (ref "R26") (pin "1") (pinfunction "1_1") (pintype "passive"))
    )
    (net (code "54") (name "Net-(VAR1-P$1)") (class "Default")
      (node (ref "SAR1") (pin "P$1") (pinfunction "P$1_P$1") (pintype "bidirectional"))
      (node (ref "VAR1") (pin "1") (pinfunction "P$1_1") (pintype "bidirectional"))
      (node (ref "VAR2") (pin "2") (pinfunction "P$2_2") (pintype "bidirectional"))
    )
    (net (code "55") (name "Net-(X4A-S)") (class "Default")
      (node (ref "C3") (pin "1") (pinfunction "1_1") (pintype "passive"))
      (node (ref "C5") (pin "+") (pinfunction "+_+") (pintype "passive"))
      (node (ref "D1") (pin "C") (pinfunction "C_C") (pintype "passive"))
      (node (ref "L1") (pin "1") (pinfunction "1_1") (pintype "passive"))
      (node (ref "R12") (pin "2") (pinfunction "2_2") (pintype "passive"))
      (node (ref "X4") (pin "1") (pinfunction "S_1") (pintype "passive"))
    )
    (net (code "56") (name "Net-(X4B-S)") (class "Default")
      (node (ref "C5") (pin "-") (pinfunction "-_-") (pintype "passive"))
      (node (ref "D1") (pin "A") (pinfunction "A_A") (pintype "passive"))
      (node (ref "Q5") (pin "2") (pinfunction "D_2") (pintype "passive"))
      (node (ref "Q5") (pin "4") (pinfunction "D_4") (pintype "passive"))
      (node (ref "X4") (pin "2") (pinfunction "S_2") (pintype "passive"))
    )
    (net (code "57") (name "Net-(X4C-S)") (class "Default")
      (node (ref "R12") (pin "1") (pinfunction "1_1") (pintype "passive"))
      (node (ref "R15") (pin "2") (pinfunction "2_2") (pintype "passive"))
      (node (ref "X4") (pin "3") (pinfunction "S_3") (pintype "passive"))
    )
    (net (code "58") (name "PE") (class "Default")
      (node (ref "J1") (pin "PE") (pinfunction "PE_PE") (pintype "bidirectional"))
      (node (ref "J2") (pin "P$1") (pinfunction "P$1_P$1") (pintype "bidirectional"))
      (node (ref "J2") (pin "P$2") (pinfunction "P$1_P$2") (pintype "bidirectional"))
      (node (ref "J3") (pin "P$1") (pinfunction "P$1_P$1") (pintype "bidirectional"))
      (node (ref "J3") (pin "P$2") (pinfunction "P$1_P$2") (pintype "bidirectional"))
      (node (ref "J4") (pin "P$1") (pinfunction "P$1_P$1") (pintype "bidirectional"))
      (node (ref "J4") (pin "P$2") (pinfunction "P$1_P$2") (pintype "bidirectional"))
      (node (ref "J5") (pin "1") (pinfunction "1_1") (pintype "passive"))
      (node (ref "J5") (pin "NC1") (pinfunction "1_NC1") (pintype "passive"))
      (node (ref "J5") (pin "NC2") (pinfunction "1_NC2") (pintype "passive"))
      (node (ref "J5") (pin "NC3") (pinfunction "1_NC3") (pintype "passive"))
      (node (ref "J5") (pin "NC4") (pinfunction "1_NC4") (pintype "passive"))
      (node (ref "JP1") (pin "NC") (pinfunction "NC_NC") (pintype "passive"))
      (node (ref "SAR1") (pin "P$2") (pinfunction "P$2_P$2") (pintype "bidirectional"))
      (node (ref "SW1") (pin "PE1") (pinfunction "PE_PE1") (pintype "power_in"))
      (node (ref "SW1") (pin "PE2") (pinfunction "PE_PE2") (pintype "power_in"))
      (node (ref "X1") (pin "3") (pinfunction "1_3") (pintype "passive"))
      (node (ref "X1") (pin "6") (pinfunction "1_6") (pintype "passive"))
      (node (ref "X2") (pin "3") (pinfunction "1_3") (pintype "passive"))
      (node (ref "X3") (pin "1") (pinfunction "1_1") (pintype "passive"))
      (node (ref "X3") (pin "2") (pinfunction "1_2") (pintype "passive"))
      (node (ref "ZD1") (pin "C") (pinfunction "1_C") (pintype "passive"))
      (node (ref "ZD2") (pin "C") (pinfunction "1_C") (pintype "passive"))
    )
    (net (code "59") (name "PWR_DIRECT") (class "Default")
      (node (ref "Q3") (pin "1") (pinfunction "G_1") (pintype "passive"))
      (node (ref "R5") (pin "2") (pinfunction "2_2") (pintype "passive"))
      (node (ref "X3") (pin "12") (pinfunction "1_12") (pintype "passive"))
    )
    (net (code "60") (name "PWR_DIR_OUT") (class "Default")
      (node (ref "Q3") (pin "3") (pinfunction "D_3") (pintype "passive"))
      (node (ref "Q6") (pin "1") (pinfunction "G_1") (pintype "passive"))
      (node (ref "R14") (pin "2") (pinfunction "2_2") (pintype "passive"))
      (node (ref "R2") (pin "2") (pinfunction "2_2") (pintype "passive"))
    )
    (net (code "61") (name "PWR_SSTART") (class "Default")
      (node (ref "Q4") (pin "1") (pinfunction "G_1") (pintype "passive"))
      (node (ref "R10") (pin "2") (pinfunction "2_2") (pintype "passive"))
      (node (ref "X3") (pin "11") (pinfunction "1_11") (pintype "passive"))
    )
    (net (code "62") (name "TEMP1_N") (class "Default")
      (node (ref "IC1") (pin "9") (pinfunction "IN-_9") (pintype "input"))
      (node (ref "X5") (pin "2") (pinfunction "S_2") (pintype "passive"))
    )
    (net (code "63") (name "TEMP1_P") (class "Default")
      (node (ref "IC1") (pin "10") (pinfunction "IN+_10") (pintype "input"))
      (node (ref "X5") (pin "1") (pinfunction "S_1") (pintype "passive"))
    )
    (net (code "64") (name "VIPER_D") (class "Default")
      (node (ref "D3") (pin "A") (pinfunction "A_A") (pintype "passive"))
      (node (ref "IC2") (pin "13") (pinfunction "DRAIN_13") (pintype "output"))
      (node (ref "IC2") (pin "14") (pinfunction "DRAIN_14") (pintype "output"))
      (node (ref "IC2") (pin "15") (pinfunction "DRAIN_15") (pintype "output"))
      (node (ref "IC2") (pin "16") (pinfunction "DRAIN_16") (pintype "output"))
      (node (ref "TR1") (pin "4") (pinfunction "P1_DOT_4") (pintype "passive"))
      (node (ref "TR1B") (pin "9") (pinfunction "P1_DOT_9") (pintype "passive"))
    )
    (net (code "65") (name "unconnected-(IC1-~{OVR}-Pad3)") (class "Default")
      (node (ref "IC1") (pin "3") (pinfunction "~{OVR}_3") (pintype "output"))
    )
    (net (code "66") (name "unconnected-(IC1-~{SMBALERT}-Pad14)") (class "Default")
      (node (ref "IC1") (pin "14") (pinfunction "~{SMBALERT}_14") (pintype "output"))
    )
    (net (code "67") (name "unconnected-(KK1-K-PadA2,5)") (class "Default")
      (node (ref "KK1") (pin "A2,5") (pinfunction "K_A2,5") (pintype "passive"))
    )
    (net (code "68") (name "unconnected-(KK1-K-PadB2,5)") (class "Default")
      (node (ref "KK1") (pin "B2,5") (pinfunction "K_B2,5") (pintype "passive"))
    )
    (net (code "69") (name "unconnected-(TR1-P1_MIDDLE-Pad3)") (class "Default")
      (node (ref "TR1") (pin "3") (pinfunction "P1_MIDDLE_3") (pintype "passive"))
    )
  )
)
